# C2Sv1_OV7670_Breakout_TopLevel.net
KiCad netlist of a schematic drawn in Altium Designer
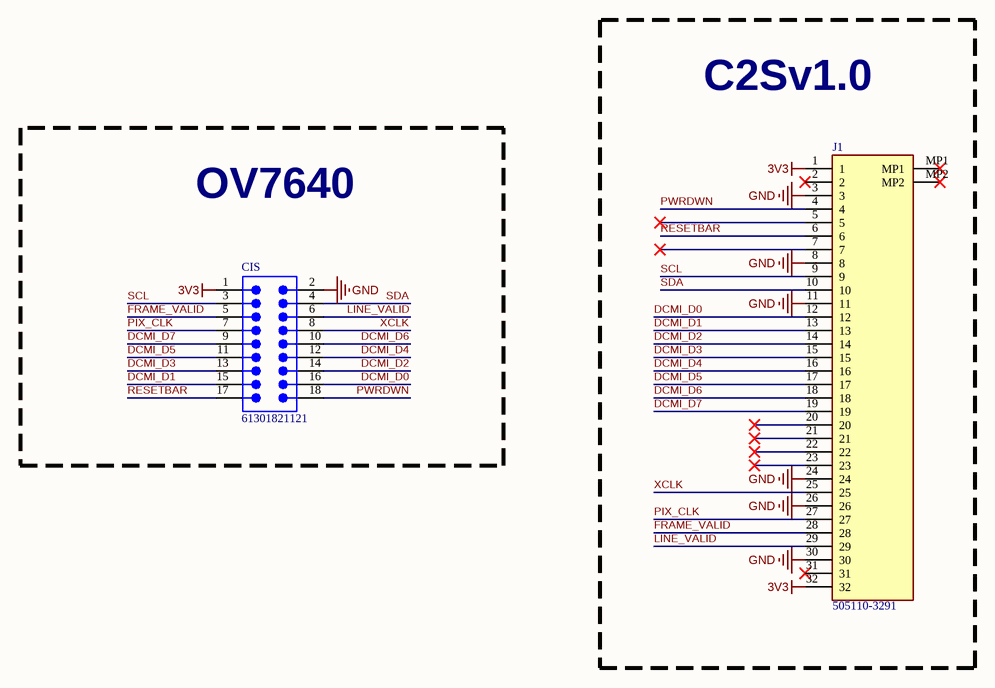
[diagram p0: C2Sv1 OV7670 Breakout_TopLevel.SchDoc]

(export (version "E")
  (design (tool "Eeschema 10.0.6"))
  (components
    (comp (ref "CIS")
      (value "61301821121")
      (footprint "61301821121")
      (description "WR-PHD Pin Header, THT, Vertical, pitch 2.54mm, 2 Row, 18P")
      (fields (field (name "MANUFACTURER") "Wurth Elektronik"))
      (libsource (lib "Perth Aerospace Student Team") (part "61301821121"))
    )
    (comp (ref "J1")
      (value "505110-3291")
      (footprint "5051103291")
      (description "Easy-On FFC/FPC Connector")
      (fields (field (name "MOUSER PART NUMBER") "538-505110-3291") (field (name "ADDED BY") "Felix Abbott"))
      (libsource (lib "Perth Aerospace Student Team") (part "505110-3291"))
    )
  )
  (nets
    (net (code "1") (name "/DCMI_D0") (class "Default")
      (node (ref "CIS") (pin "16") (pinfunction "16_16") (pintype "passive"))
      (node (ref "J1") (pin "12") (pinfunction "12_12") (pintype "passive"))
    )
    (net (code "2") (name "/DCMI_D1") (class "Default")
      (node (ref "CIS") (pin "15") (pinfunction "15_15") (pintype "passive"))
      (node (ref "J1") (pin "13") (pinfunction "13_13") (pintype "passive"))
    )
    (net (code "3") (name "/DCMI_D2") (class "Default")
      (node (ref "CIS") (pin "14") (pinfunction "14_14") (pintype "passive"))
      (node (ref "J1") (pin "14") (pinfunction "14_14") (pintype "passive"))
    )
    (net (code "4") (name "/DCMI_D3") (class "Default")
      (node (ref "CIS") (pin "13") (pinfunction "13_13") (pintype "passive"))
      (node (ref "J1") (pin "15") (pinfunction "15_15") (pintype "passive"))
    )
    (net (code "5") (name "/DCMI_D4") (class "Default")
      (node (ref "CIS") (pin "12") (pinfunction "12_12") (pintype "passive"))
      (node (ref "J1") (pin "16") (pinfunction "16_16") (pintype "passive"))
    )
    (net (code "6") (name "/DCMI_D5") (class "Default")
      (node (ref "CIS") (pin "11") (pinfunction "11_11") (pintype "passive"))
      (node (ref "J1") (pin "17") (pinfunction "17_17") (pintype "passive"))
    )
    (net (code "7") (name "/DCMI_D6") (class "Default")
      (node (ref "CIS") (pin "10") (pinfunction "10_10") (pintype "passive"))
      (node (ref "J1") (pin "18") (pinfunction "18_18") (pintype "passive"))
    )
    (net (code "8") (name "/DCMI_D7") (class "Default")
      (node (ref "CIS") (pin "9") (pinfunction "9_9") (pintype "passive"))
      (node (ref "J1") (pin "19") (pinfunction "19_19") (pintype "passive"))
    )
    (net (code "9") (name "/FRAME_VALID") (class "Default")
      (node (ref "CIS") (pin "5") (pinfunction "5_5") (pintype "passive"))
      (node (ref "J1") (pin "28") (pinfunction "28_28") (pintype "passive"))
    )
    (net (code "10") (name "/LINE_VALID") (class "Default")
      (node (ref "CIS") (pin "6") (pinfunction "6_6") (pintype "passive"))
      (node (ref "J1") (pin "29") (pinfunction "29_29") (pintype "passive"))
    )
    (net (code "11") (name "/PIX_CLK") (class "Default")
      (node (ref "CIS") (pin "7") (pinfunction "7_7") (pintype "passive"))
      (node (ref "J1") (pin "27") (pinfunction "27_27") (pintype "passive"))
    )
    (net (code "12") (name "/PWRDWN") (class "Default")
      (node (ref "CIS") (pin "18") (pinfunction "18_18") (pintype "passive"))
      (node (ref "J1") (pin "4") (pinfunction "4_4") (pintype "passive"))
    )
    (net (code "13") (name "/RESETBAR") (class "Default")
      (node (ref "CIS") (pin "17") (pinfunction "17_17") (pintype "passive"))
      (node (ref "J1") (pin "6") (pinfunction "6_6") (pintype "passive"))
    )
    (net (code "14") (name "/SCL") (class "Default")
      (node (ref "CIS") (pin "3") (pinfunction "3_3") (pintype "passive"))
      (node (ref "J1") (pin "9") (pinfunction "9_9") (pintype "passive"))
    )
    (net (code "15") (name "/SDA") (class "Default")
      (node (ref "CIS") (pin "4") (pinfunction "4_4") (pintype "passive"))
      (node (ref "J1") (pin "10") (pinfunction "10_10") (pintype "passive"))
    )
    (net (code "16") (name "/XCLK") (class "Default")
      (node (ref "CIS") (pin "8") (pinfunction "8_8") (pintype "passive"))
      (node (ref "J1") (pin "25") (pinfunction "25_25") (pintype "passive"))
    )
    (net (code "17") (name "3V3") (class "Default")
      (node (ref "CIS") (pin "1") (pinfunction "1_1") (pintype "passive"))
      (node (ref "J1") (pin "1") (pinfunction "1_1") (pintype "passive"))
      (node (ref "J1") (pin "32") (pinfunction "32_32") (pintype "passive"))
    )
    (net (code "18") (name "GND") (class "Default")
      (node (ref "CIS") (pin "2") (pinfunction "2_2") (pintype "passive"))
      (node (ref "J1") (pin "11") (pinfunction "11_11") (pintype "passive"))
      (node (ref "J1") (pin "24") (pinfunction "24_24") (pintype "passive"))
      (node (ref "J1") (pin "26") (pinfunction "26_26") (pintype "passive"))
      (node (ref "J1") (pin "3") (pinfunction "3_3") (pintype "passive"))
      (node (ref "J1") (pin "30") (pinfunction "30_30") (pintype "passive"))
      (node (ref "J1") (pin "8") (pinfunction "8_8") (pintype "passive"))
    )
    (net (code "19") (name "unconnected-(J1-Pad2)") (class "Default")
      (node (ref "J1") (pin "2") (pinfunction "2_2") (pintype "passive+no_connect"))
    )
    (net (code "20") (name "unconnected-(J1-Pad5)") (class "Default")
      (node (ref "J1") (pin "5") (pinfunction "5_5") (pintype "passive+no_connect"))
    )
    (net (code "21") (name "unconnected-(J1-Pad7)") (class "Default")
      (node (ref "J1") (pin "7") (pinfunction "7_7") (pintype "passive+no_connect"))
    )
    (net (code "22") (name "unconnected-(J1-Pad20)") (class "Default")
      (node (ref "J1") (pin "20") (pinfunction "20_20") (pintype "passive+no_connect"))
    )
    (net (code "23") (name "unconnected-(J1-Pad21)") (class "Default")
      (node (ref "J1") (pin "21") (pinfunction "21_21") (pintype "passive+no_connect"))
    )
    (net (code "24") (name "unconnected-(J1-Pad22)") (class "Default")
      (node (ref "J1") (pin "22") (pinfunction "22_22") (pintype "passive+no_connect"))
    )
    (net (code "25") (name "unconnected-(J1-Pad23)") (class "Default")
      (node (ref "J1") (pin "23") (pinfunction "23_23") (pintype "passive+no_connect"))
    )
    (net (code "26") (name "unconnected-(J1-Pad31)") (class "Default")
      (node (ref "J1") (pin "31") (pinfunction "31_31") (pintype "passive+no_connect"))
    )
    (net (code "27") (name "unconnected-(J1-PadMP1)") (class "Default")
      (node (ref "J1") (pin "MP1") (pinfunction "MP1_MP1") (pintype "passive+no_connect"))
    )
    (net (code "28") (name "unconnected-(J1-PadMP2)") (class "Default")
      (node (ref "J1") (pin "MP2") (pinfunction "MP2_MP2") (pintype "passive+no_connect"))
    )
  )
)
